# LED__V1_0.net
KiCad netlist of a schematic drawn in Altium Designer
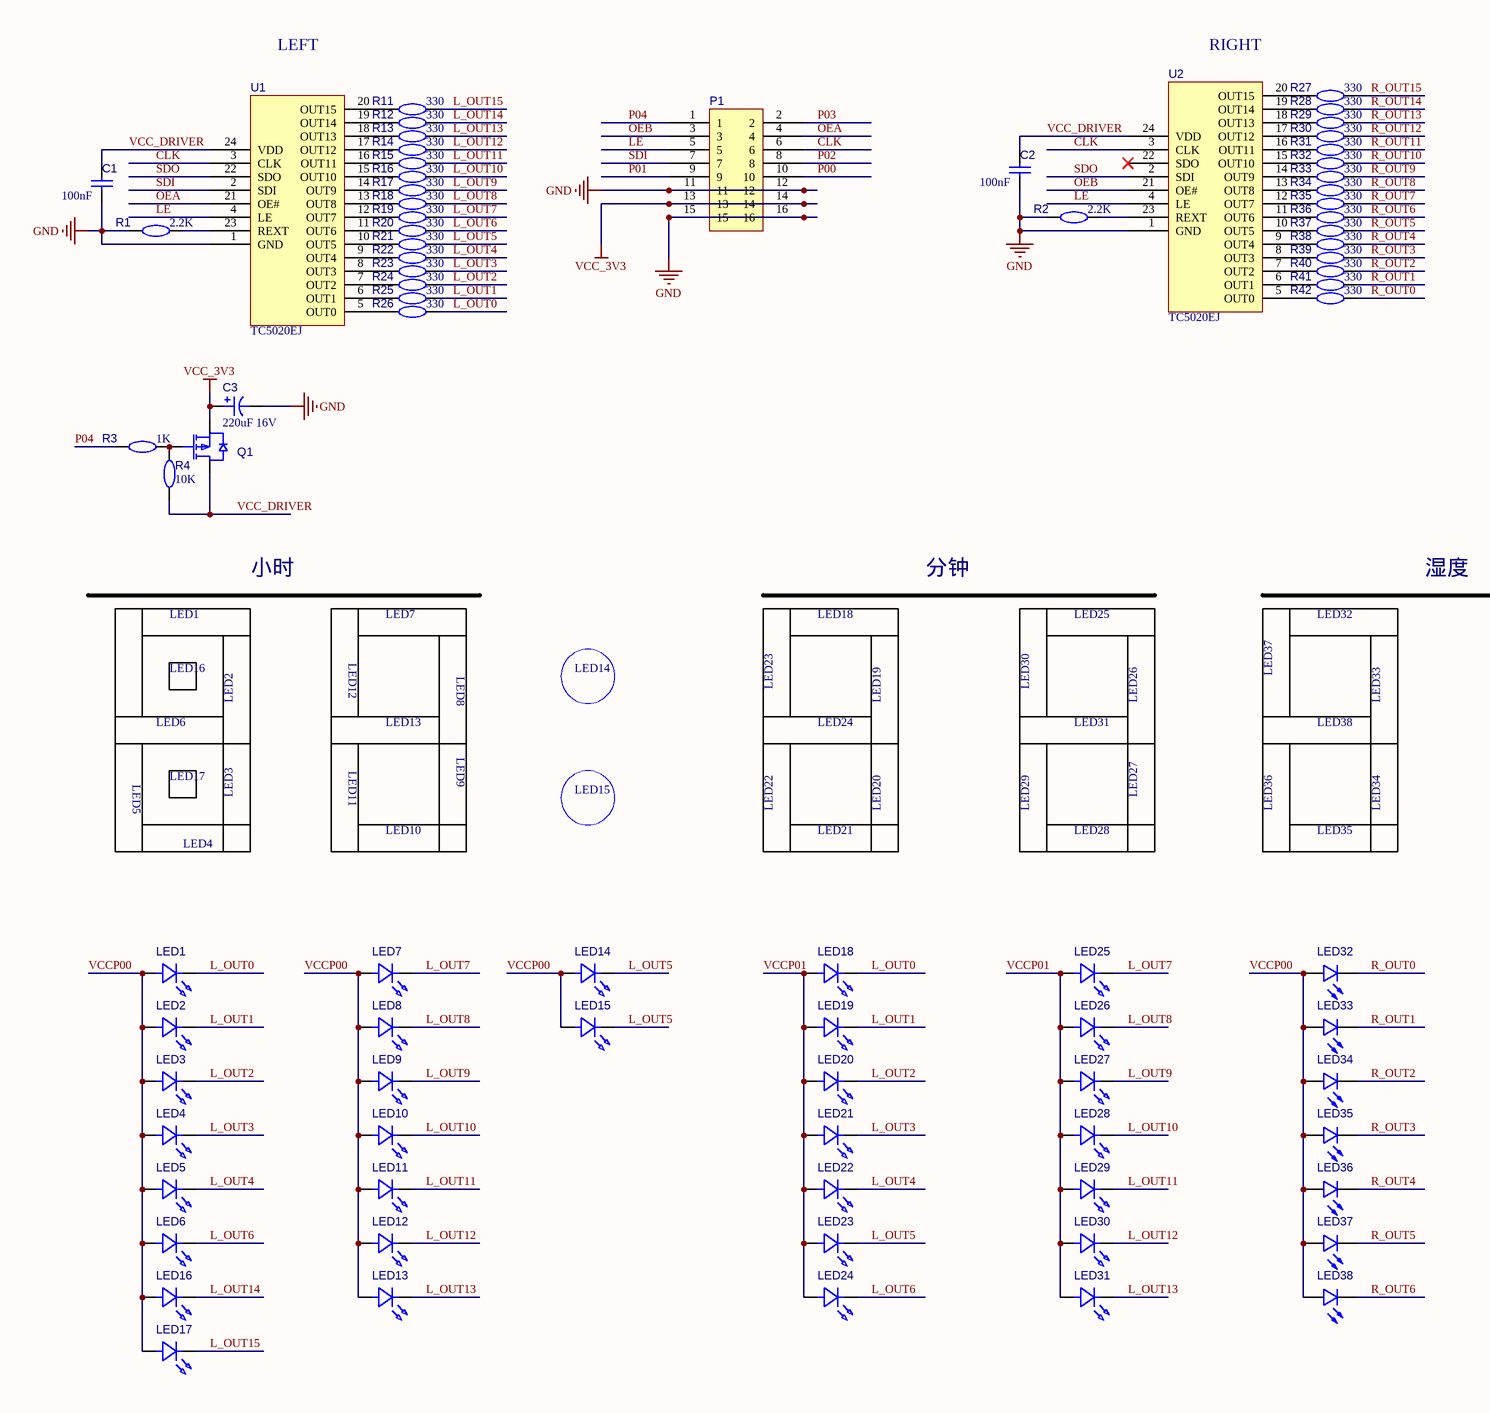
[diagram p0: LED显示灯板_V1.0.SchDoc, left]
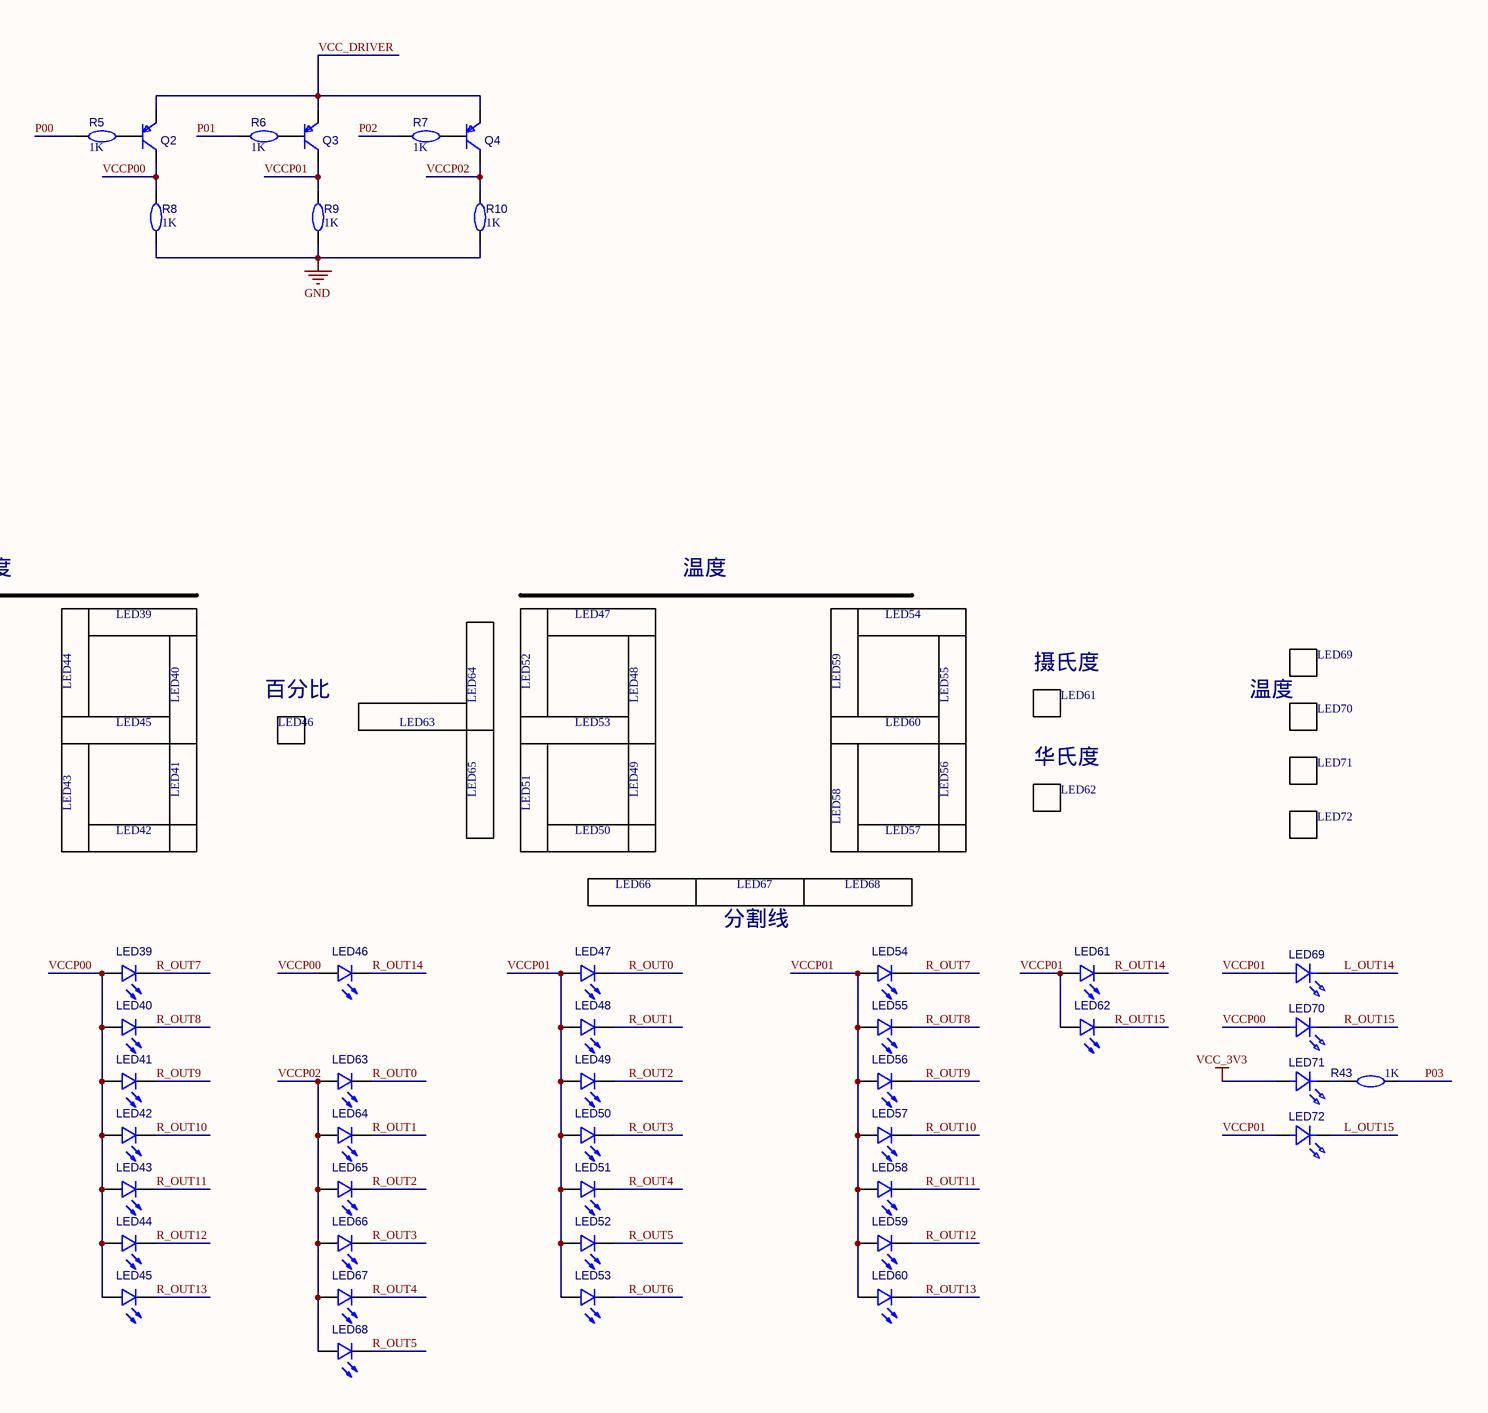
[diagram p1: LED显示灯板_V1.0.SchDoc, right]

(export (version "E")
  (design (tool "Eeschema 10.0.6"))
  (components
    (comp (ref "C1")
      (value "100nF")
      (footprint "C0603")
      (description "贴片电容")
      (libsource (lib "ADlib") (part "CAP_C0603_50V_10nF 50V"))
    )
    (comp (ref "C2")
      (value "100nF")
      (footprint "C0603")
      (description "贴片电容")
      (libsource (lib "ADlib") (part "CAP_C0603_50V_10nF 50V"))
    )
    (comp (ref "C3")
      (value "220uF 16V")
      (footprint "CAP-SMD_BD6.3-L6.6-W6.6-FD-1")
      (description "贴片型铝电解电容")
      (libsource (lib "ADlib") (part "CAP_ELEC_SMD_220U_16V"))
    )
    (comp (ref "LED1")
      (value "LED_WHITE_20MA_TBD")
      (footprint "LED0603")
      (description "发光二极管")
      (libsource (lib "ADlib") (part "LED_WHITE_20MA_TBD"))
    )
    (comp (ref "LED2")
      (value "LED_WHITE_20MA_TBD")
      (footprint "LED0603")
      (description "发光二极管")
      (libsource (lib "ADlib") (part "LED_WHITE_20MA_TBD"))
    )
    (comp (ref "LED3")
      (value "LED_WHITE_20MA_TBD")
      (footprint "LED0603")
      (description "发光二极管")
      (libsource (lib "ADlib") (part "LED_WHITE_20MA_TBD"))
    )
    (comp (ref "LED4")
      (value "LED_WHITE_20MA_TBD")
      (footprint "LED0603")
      (description "发光二极管")
      (libsource (lib "ADlib") (part "LED_WHITE_20MA_TBD"))
    )
    (comp (ref "LED5")
      (value "LED_WHITE_20MA_TBD")
      (footprint "LED0603")
      (description "发光二极管")
      (libsource (lib "ADlib") (part "LED_WHITE_20MA_TBD"))
    )
    (comp (ref "LED6")
      (value "LED_WHITE_20MA_TBD")
      (footprint "LED0603")
      (description "发光二极管")
      (libsource (lib "ADlib") (part "LED_WHITE_20MA_TBD"))
    )
    (comp (ref "LED7")
      (value "LED_WHITE_20MA_TBD")
      (footprint "LED0603")
      (description "发光二极管")
      (libsource (lib "ADlib") (part "LED_WHITE_20MA_TBD"))
    )
    (comp (ref "LED8")
      (value "LED_WHITE_20MA_TBD")
      (footprint "LED0603")
      (description "发光二极管")
      (libsource (lib "ADlib") (part "LED_WHITE_20MA_TBD"))
    )
    (comp (ref "LED9")
      (value "LED_WHITE_20MA_TBD")
      (footprint "LED0603")
      (description "发光二极管")
      (libsource (lib "ADlib") (part "LED_WHITE_20MA_TBD"))
    )
    (comp (ref "LED10")
      (value "LED_WHITE_20MA_TBD")
      (footprint "LED0603")
      (description "发光二极管")
      (libsource (lib "ADlib") (part "LED_WHITE_20MA_TBD"))
    )
    (comp (ref "LED11")
      (value "LED_WHITE_20MA_TBD")
      (footprint "LED0603")
      (description "发光二极管")
      (libsource (lib "ADlib") (part "LED_WHITE_20MA_TBD"))
    )
    (comp (ref "LED12")
      (value "LED_WHITE_20MA_TBD")
      (footprint "LED0603")
      (description "发光二极管")
      (libsource (lib "ADlib") (part "LED_WHITE_20MA_TBD"))
    )
    (comp (ref "LED13")
      (value "LED_WHITE_20MA_TBD")
      (footprint "LED0603")
      (description "发光二极管")
      (libsource (lib "ADlib") (part "LED_WHITE_20MA_TBD"))
    )
    (comp (ref "LED14")
      (value "LED_WHITE_20MA_TBD")
      (footprint "LED0603")
      (description "发光二极管")
      (libsource (lib "ADlib") (part "LED_WHITE_20MA_TBD"))
    )
    (comp (ref "LED15")
      (value "LED_WHITE_20MA_TBD")
      (footprint "LED0603")
      (description "发光二极管")
      (libsource (lib "ADlib") (part "LED_WHITE_20MA_TBD"))
    )
    (comp (ref "LED16")
      (value "LED_WHITE_20MA_TBD")
      (footprint "LED0603")
      (description "发光二极管")
      (libsource (lib "ADlib") (part "LED_WHITE_20MA_TBD"))
    )
    (comp (ref "LED17")
      (value "LED_WHITE_20MA_TBD")
      (footprint "LED0603")
      (description "发光二极管")
      (libsource (lib "ADlib") (part "LED_WHITE_20MA_TBD"))
    )
    (comp (ref "LED18")
      (value "LED_WHITE_20MA_TBD")
      (footprint "LED0603")
      (description "发光二极管")
      (libsource (lib "ADlib") (part "LED_WHITE_20MA_TBD"))
    )
    (comp (ref "LED19")
      (value "LED_WHITE_20MA_TBD")
      (footprint "LED0603")
      (description "发光二极管")
      (libsource (lib "ADlib") (part "LED_WHITE_20MA_TBD"))
    )
    (comp (ref "LED20")
      (value "LED_WHITE_20MA_TBD")
      (footprint "LED0603")
      (description "发光二极管")
      (libsource (lib "ADlib") (part "LED_WHITE_20MA_TBD"))
    )
    (comp (ref "LED21")
      (value "LED_WHITE_20MA_TBD")
      (footprint "LED0603")
      (description "发光二极管")
      (libsource (lib "ADlib") (part "LED_WHITE_20MA_TBD"))
    )
    (comp (ref "LED22")
      (value "LED_WHITE_20MA_TBD")
      (footprint "LED0603")
      (description "发光二极管")
      (libsource (lib "ADlib") (part "LED_WHITE_20MA_TBD"))
    )
    (comp (ref "LED23")
      (value "LED_WHITE_20MA_TBD")
      (footprint "LED0603")
      (description "发光二极管")
      (libsource (lib "ADlib") (part "LED_WHITE_20MA_TBD"))
    )
    (comp (ref "LED24")
      (value "LED_WHITE_20MA_TBD")
      (footprint "LED0603")
      (description "发光二极管")
      (libsource (lib "ADlib") (part "LED_WHITE_20MA_TBD"))
    )
    (comp (ref "LED25")
      (value "LED_WHITE_20MA_TBD")
      (footprint "LED0603")
      (description "发光二极管")
      (libsource (lib "ADlib") (part "LED_WHITE_20MA_TBD"))
    )
    (comp (ref "LED26")
      (value "LED_WHITE_20MA_TBD")
      (footprint "LED0603")
      (description "发光二极管")
      (libsource (lib "ADlib") (part "LED_WHITE_20MA_TBD"))
    )
    (comp (ref "LED27")
      (value "LED_WHITE_20MA_TBD")
      (footprint "LED0603")
      (description "发光二极管")
      (libsource (lib "ADlib") (part "LED_WHITE_20MA_TBD"))
    )
    (comp (ref "LED28")
      (value "LED_WHITE_20MA_TBD")
      (footprint "LED0603")
      (description "发光二极管")
      (libsource (lib "ADlib") (part "LED_WHITE_20MA_TBD"))
    )
    (comp (ref "LED29")
      (value "LED_WHITE_20MA_TBD")
      (footprint "LED0603")
      (description "发光二极管")
      (libsource (lib "ADlib") (part "LED_WHITE_20MA_TBD"))
    )
    (comp (ref "LED30")
      (value "LED_WHITE_20MA_TBD")
      (footprint "LED0603")
      (description "发光二极管")
      (libsource (lib "ADlib") (part "LED_WHITE_20MA_TBD"))
    )
    (comp (ref "LED31")
      (value "LED_WHITE_20MA_TBD")
      (footprint "LED0603")
      (description "发光二极管")
      (libsource (lib "ADlib") (part "LED_WHITE_20MA_TBD"))
    )
    (comp (ref "LED32")
      (value "LED BLUE")
      (footprint "LED0603")
      (description "发光二极管")
      (libsource (lib "ADlib") (part "LED_BLUE_10MA_TBD"))
    )
    (comp (ref "LED33")
      (value "LED BLUE")
      (footprint "LED0603")
      (description "发光二极管")
      (libsource (lib "ADlib") (part "LED_BLUE_10MA_TBD"))
    )
    (comp (ref "LED34")
      (value "LED BLUE")
      (footprint "LED0603")
      (description "发光二极管")
      (libsource (lib "ADlib") (part "LED_BLUE_10MA_TBD"))
    )
    (comp (ref "LED35")
      (value "LED BLUE")
      (footprint "LED0603")
      (description "发光二极管")
      (libsource (lib "ADlib") (part "LED_BLUE_10MA_TBD"))
    )
    (comp (ref "LED36")
      (value "LED BLUE")
      (footprint "LED0603")
      (description "发光二极管")
      (libsource (lib "ADlib") (part "LED_BLUE_10MA_TBD"))
    )
    (comp (ref "LED37")
      (value "LED BLUE")
      (footprint "LED0603")
      (description "发光二极管")
      (libsource (lib "ADlib") (part "LED_BLUE_10MA_TBD"))
    )
    (comp (ref "LED38")
      (value "LED BLUE")
      (footprint "LED0603")
      (description "发光二极管")
      (libsource (lib "ADlib") (part "LED_BLUE_10MA_TBD"))
    )
    (comp (ref "LED39")
      (value "LED BLUE")
      (footprint "LED0603")
      (description "发光二极管")
      (libsource (lib "ADlib") (part "LED_BLUE_10MA_TBD"))
    )
    (comp (ref "LED40")
      (value "LED BLUE")
      (footprint "LED0603")
      (description "发光二极管")
      (libsource (lib "ADlib") (part "LED_BLUE_10MA_TBD"))
    )
    (comp (ref "LED41")
      (value "LED BLUE")
      (footprint "LED0603")
      (description "发光二极管")
      (libsource (lib "ADlib") (part "LED_BLUE_10MA_TBD"))
    )
    (comp (ref "LED42")
      (value "LED BLUE")
      (footprint "LED0603")
      (description "发光二极管")
      (libsource (lib "ADlib") (part "LED_BLUE_10MA_TBD"))
    )
    (comp (ref "LED43")
      (value "LED BLUE")
      (footprint "LED0603")
      (description "发光二极管")
      (libsource (lib "ADlib") (part "LED_BLUE_10MA_TBD"))
    )
    (comp (ref "LED44")
      (value "LED BLUE")
      (footprint "LED0603")
      (description "发光二极管")
      (libsource (lib "ADlib") (part "LED_BLUE_10MA_TBD"))
    )
    (comp (ref "LED45")
      (value "LED BLUE")
      (footprint "LED0603")
      (description "发光二极管")
      (libsource (lib "ADlib") (part "LED_BLUE_10MA_TBD"))
    )
    (comp (ref "LED46")
      (value "LED BLUE")
      (footprint "LED0603")
      (description "发光二极管")
      (libsource (lib "ADlib") (part "LED_BLUE_10MA_TBD"))
    )
    (comp (ref "LED47")
      (value "LED BLUE")
      (footprint "LED0603")
      (description "发光二极管")
      (libsource (lib "ADlib") (part "LED_BLUE_10MA_TBD"))
    )
    (comp (ref "LED48")
      (value "LED BLUE")
      (footprint "LED0603")
      (description "发光二极管")
      (libsource (lib "ADlib") (part "LED_BLUE_10MA_TBD"))
    )
    (comp (ref "LED49")
      (value "LED BLUE")
      (footprint "LED0603")
      (description "发光二极管")
      (libsource (lib "ADlib") (part "LED_BLUE_10MA_TBD"))
    )
    (comp (ref "LED50")
      (value "LED BLUE")
      (footprint "LED0603")
      (description "发光二极管")
      (libsource (lib "ADlib") (part "LED_BLUE_10MA_TBD"))
    )
    (comp (ref "LED51")
      (value "LED BLUE")
      (footprint "LED0603")
      (description "发光二极管")
      (libsource (lib "ADlib") (part "LED_BLUE_10MA_TBD"))
    )
    (comp (ref "LED52")
      (value "LED BLUE")
      (footprint "LED0603")
      (description "发光二极管")
      (libsource (lib "ADlib") (part "LED_BLUE_10MA_TBD"))
    )
    (comp (ref "LED53")
      (value "LED BLUE")
      (footprint "LED0603")
      (description "发光二极管")
      (libsource (lib "ADlib") (part "LED_BLUE_10MA_TBD"))
    )
    (comp (ref "LED54")
      (value "LED BLUE")
      (footprint "LED0603")
      (description "发光二极管")
      (libsource (lib "ADlib") (part "LED_BLUE_10MA_TBD"))
    )
    (comp (ref "LED55")
      (value "LED BLUE")
      (footprint "LED0603")
      (description "发光二极管")
      (libsource (lib "ADlib") (part "LED_BLUE_10MA_TBD"))
    )
    (comp (ref "LED56")
      (value "LED BLUE")
      (footprint "LED0603")
      (description "发光二极管")
      (libsource (lib "ADlib") (part "LED_BLUE_10MA_TBD"))
    )
    (comp (ref "LED57")
      (value "LED BLUE")
      (footprint "LED0603")
      (description "发光二极管")
      (libsource (lib "ADlib") (part "LED_BLUE_10MA_TBD"))
    )
    (comp (ref "LED58")
      (value "LED BLUE")
      (footprint "LED0603")
      (description "发光二极管")
      (libsource (lib "ADlib") (part "LED_BLUE_10MA_TBD"))
    )
    (comp (ref "LED59")
      (value "LED BLUE")
      (footprint "LED0603")
      (description "发光二极管")
      (libsource (lib "ADlib") (part "LED_BLUE_10MA_TBD"))
    )
    (comp (ref "LED60")
      (value "LED BLUE")
      (footprint "LED0603")
      (description "发光二极管")
      (libsource (lib "ADlib") (part "LED_BLUE_10MA_TBD"))
    )
    (comp (ref "LED61")
      (value "LED BLUE")
      (footprint "LED0603")
      (description "发光二极管")
      (libsource (lib "ADlib") (part "LED_BLUE_10MA_TBD"))
    )
    (comp (ref "LED62")
      (value "LED BLUE")
      (footprint "LED0603")
      (description "发光二极管")
      (libsource (lib "ADlib") (part "LED_BLUE_10MA_TBD"))
    )
    (comp (ref "LED63")
      (value "LED BLUE")
      (footprint "LED0603")
      (description "发光二极管")
      (libsource (lib "ADlib") (part "LED_BLUE_10MA_TBD"))
    )
    (comp (ref "LED64")
      (value "LED BLUE")
      (footprint "LED0603")
      (description "发光二极管")
      (libsource (lib "ADlib") (part "LED_BLUE_10MA_TBD"))
    )
    (comp (ref "LED65")
      (value "LED BLUE")
      (footprint "LED0603")
      (description "发光二极管")
      (libsource (lib "ADlib") (part "LED_BLUE_10MA_TBD"))
    )
    (comp (ref "LED66")
      (value "LED BLUE")
      (footprint "LED0603")
      (description "发光二极管")
      (libsource (lib "ADlib") (part "LED_BLUE_10MA_TBD"))
    )
    (comp (ref "LED67")
      (value "LED BLUE")
      (footprint "LED0603")
      (description "发光二极管")
      (libsource (lib "ADlib") (part "LED_BLUE_10MA_TBD"))
    )
    (comp (ref "LED68")
      (value "LED BLUE")
      (footprint "LED0603")
      (description "发光二极管")
      (libsource (lib "ADlib") (part "LED_BLUE_10MA_TBD"))
    )
    (comp (ref "LED69")
      (value "LED_WHITE_20MA_TBD")
      (footprint "LED0603")
      (description "发光二极管")
      (libsource (lib "ADlib") (part "LED_WHITE_20MA_TBD"))
    )
    (comp (ref "LED70")
      (value "LED_WHITE_20MA_TBD")
      (footprint "LED0603")
      (description "发光二极管")
      (libsource (lib "ADlib") (part "LED_WHITE_20MA_TBD"))
    )
    (comp (ref "LED71")
      (value "LED_WHITE_20MA_TBD")
      (footprint "LED0603")
      (description "发光二极管")
      (libsource (lib "ADlib") (part "LED_WHITE_20MA_TBD"))
    )
    (comp (ref "LED72")
      (value "LED_WHITE_20MA_TBD")
      (footprint "LED0603")
      (description "发光二极管")
      (libsource (lib "ADlib") (part "LED_WHITE_20MA_TBD"))
    )
    (comp (ref "P1")
      (value "HEADER 2x8P 2.54mm")
      (footprint "IDC-TH_16P-P2.54-V-R2-C8-S2.54")
      (description "简牛座")
      (libsource (lib "ADlib") (part "HDR_2x08_2.54mm_IDC"))
    )
    (comp (ref "Q1")
      (value "P-MOSFET 30V 4A")
      (footprint "SOT-23_L2.9-W1.3-P1.90-LS2.4-BR")
      (description "P沟道场效应管")
      (libsource (lib "ADlib") (part "AO3401A"))
    )
    (comp (ref "Q2")
      (value "S8550")
      (footprint "SOT-23-3_L2.9-W1.3-P1.90-LS2.4-BR")
      (description "三极管PNP")
      (libsource (lib "ADlib") (part "S8550"))
    )
    (comp (ref "Q3")
      (value "S8550")
      (footprint "SOT-23-3_L2.9-W1.3-P1.90-LS2.4-BR")
      (description "三极管PNP")
      (libsource (lib "ADlib") (part "S8550"))
    )
    (comp (ref "Q4")
      (value "S8550")
      (footprint "SOT-23-3_L2.9-W1.3-P1.90-LS2.4-BR")
      (description "三极管PNP")
      (libsource (lib "ADlib") (part "S8550"))
    )
    (comp (ref "R1")
      (value "2.2K")
      (footprint "R0603")
      (description "贴片电阻")
      (libsource (lib "ADlib") (part "R_0603_100MW"))
    )
    (comp (ref "R2")
      (value "2.2K")
      (footprint "R0603")
      (description "贴片电阻")
      (libsource (lib "ADlib") (part "R_0603_100MW"))
    )
    (comp (ref "R3")
      (value "1K")
      (footprint "R0603")
      (description "贴片电阻")
      (libsource (lib "ADlib") (part "R_0603_100MW"))
    )
    (comp (ref "R4")
      (value "10K")
      (footprint "R0603")
      (description "贴片电阻")
      (libsource (lib "ADlib") (part "R_0603_100MW"))
    )
    (comp (ref "R5")
      (value "1K")
      (footprint "R0603")
      (description "贴片电阻")
      (libsource (lib "ADlib") (part "R_0603_100MW"))
    )
    (comp (ref "R6")
      (value "1K")
      (footprint "R0603")
      (description "贴片电阻")
      (libsource (lib "ADlib") (part "R_0603_100MW"))
    )
    (comp (ref "R7")
      (value "1K")
      (footprint "R0603")
      (description "贴片电阻")
      (libsource (lib "ADlib") (part "R_0603_100MW"))
    )
    (comp (ref "R8")
      (value "1K")
      (footprint "R0603")
      (description "贴片电阻")
      (libsource (lib "ADlib") (part "R_0603_100MW"))
    )
    (comp (ref "R9")
      (value "1K")
      (footprint "R0603")
      (description "贴片电阻")
      (libsource (lib "ADlib") (part "R_0603_100MW"))
    )
    (comp (ref "R10")
      (value "1K")
      (footprint "R0603")
      (description "贴片电阻")
      (libsource (lib "ADlib") (part "R_0603_100MW"))
    )
    (comp (ref "R11")
      (value "330")
      (footprint "R0603")
      (description "贴片电阻")
      (libsource (lib "ADlib") (part "R_0603_100MW"))
    )
    (comp (ref "R12")
      (value "330")
      (footprint "R0603")
      (description "贴片电阻")
      (libsource (lib "ADlib") (part "R_0603_100MW"))
    )
    (comp (ref "R13")
      (value "330")
      (footprint "R0603")
      (description "贴片电阻")
      (libsource (lib "ADlib") (part "R_0603_100MW"))
    )
    (comp (ref "R14")
      (value "330")
      (footprint "R0603")
      (description "贴片电阻")
      (libsource (lib "ADlib") (part "R_0603_100MW"))
    )
    (comp (ref "R15")
      (value "330")
      (footprint "R0603")
      (description "贴片电阻")
      (libsource (lib "ADlib") (part "R_0603_100MW"))
    )
    (comp (ref "R16")
      (value "330")
      (footprint "R0603")
      (description "贴片电阻")
      (libsource (lib "ADlib") (part "R_0603_100MW"))
    )
    (comp (ref "R17")
      (value "330")
      (footprint "R0603")
      (description "贴片电阻")
      (libsource (lib "ADlib") (part "R_0603_100MW"))
    )
    (comp (ref "R18")
      (value "330")
      (footprint "R0603")
      (description "贴片电阻")
      (libsource (lib "ADlib") (part "R_0603_100MW"))
    )
    (comp (ref "R19")
      (value "330")
      (footprint "R0603")
      (description "贴片电阻")
      (libsource (lib "ADlib") (part "R_0603_100MW"))
    )
    (comp (ref "R20")
      (value "330")
      (footprint "R0603")
      (description "贴片电阻")
      (libsource (lib "ADlib") (part "R_0603_100MW"))
    )
    (comp (ref "R21")
      (value "330")
      (footprint "R0603")
      (description "贴片电阻")
      (libsource (lib "ADlib") (part "R_0603_100MW"))
    )
    (comp (ref "R22")
      (value "330")
      (footprint "R0603")
      (description "贴片电阻")
      (libsource (lib "ADlib") (part "R_0603_100MW"))
    )
    (comp (ref "R23")
      (value "330")
      (footprint "R0603")
      (description "贴片电阻")
      (libsource (lib "ADlib") (part "R_0603_100MW"))
    )
    (comp (ref "R24")
      (value "330")
      (footprint "R0603")
      (description "贴片电阻")
      (libsource (lib "ADlib") (part "R_0603_100MW"))
    )
    (comp (ref "R25")
      (value "330")
      (footprint "R0603")
      (description "贴片电阻")
      (libsource (lib "ADlib") (part "R_0603_100MW"))
    )
    (comp (ref "R26")
      (value "330")
      (footprint "R0603")
      (description "贴片电阻")
      (libsource (lib "ADlib") (part "R_0603_100MW"))
    )
    (comp (ref "R27")
      (value "330")
      (footprint "R0603")
      (description "贴片电阻")
      (libsource (lib "ADlib") (part "R_0603_100MW"))
    )
    (comp (ref "R28")
      (value "330")
      (footprint "R0603")
      (description "贴片电阻")
      (libsource (lib "ADlib") (part "R_0603_100MW"))
    )
    (comp (ref "R29")
      (value "330")
      (footprint "R0603")
      (description "贴片电阻")
      (libsource (lib "ADlib") (part "R_0603_100MW"))
    )
    (comp (ref "R30")
      (value "330")
      (footprint "R0603")
      (description "贴片电阻")
      (libsource (lib "ADlib") (part "R_0603_100MW"))
    )
    (comp (ref "R31")
      (value "330")
      (footprint "R0603")
      (description "贴片电阻")
      (libsource (lib "ADlib") (part "R_0603_100MW"))
    )
    (comp (ref "R32")
      (value "330")
      (footprint "R0603")
      (description "贴片电阻")
      (libsource (lib "ADlib") (part "R_0603_100MW"))
    )
    (comp (ref "R33")
      (value "330")
      (footprint "R0603")
      (description "贴片电阻")
      (libsource (lib "ADlib") (part "R_0603_100MW"))
    )
    (comp (ref "R34")
      (value "330")
      (footprint "R0603")
      (description "贴片电阻")
      (libsource (lib "ADlib") (part "R_0603_100MW"))
    )
    (comp (ref "R35")
      (value "330")
      (footprint "R0603")
      (description "贴片电阻")
      (libsource (lib "ADlib") (part "R_0603_100MW"))
    )
    (comp (ref "R36")
      (value "330")
      (footprint "R0603")
      (description "贴片电阻")
      (libsource (lib "ADlib") (part "R_0603_100MW"))
    )
    (comp (ref "R37")
      (value "330")
      (footprint "R0603")
      (description "贴片电阻")
      (libsource (lib "ADlib") (part "R_0603_100MW"))
    )
    (comp (ref "R38")
      (value "330")
      (footprint "R0603")
      (description "贴片电阻")
      (libsource (lib "ADlib") (part "R_0603_100MW"))
    )
    (comp (ref "R39")
      (value "330")
      (footprint "R0603")
      (description "贴片电阻")
      (libsource (lib "ADlib") (part "R_0603_100MW"))
    )
    (comp (ref "R40")
      (value "330")
      (footprint "R0603")
      (description "贴片电阻")
      (libsource (lib "ADlib") (part "R_0603_100MW"))
    )
    (comp (ref "R41")
      (value "330")
      (footprint "R0603")
      (description "贴片电阻")
      (libsource (lib "ADlib") (part "R_0603_100MW"))
    )
    (comp (ref "R42")
      (value "330")
      (footprint "R0603")
      (description "贴片电阻")
      (libsource (lib "ADlib") (part "R_0603_100MW"))
    )
    (comp (ref "R43")
      (value "1K")
      (footprint "R0603")
      (description "贴片电阻")
      (libsource (lib "ADlib") (part "R_0603_100MW"))
    )
    (comp (ref "U1")
      (value "TC5020EJ")
      (footprint "SSOP-24_L8.7-W3.9-P0.64-LS6.0-BL")
      (description "LED 驱动芯片")
      (libsource (lib "ADlib") (part "TC5020EJ"))
    )
    (comp (ref "U2")
      (value "TC5020EJ")
      (footprint "SSOP-24_L8.7-W3.9-P0.64-LS6.0-BL")
      (description "LED 驱动芯片")
      (libsource (lib "ADlib") (part "TC5020EJ"))
    )
  )
  (nets
    (net (code "1") (name "/CLK") (class "Default")
      (node (ref "P1") (pin "6") (pinfunction "6_6") (pintype "passive"))
      (node (ref "U1") (pin "3") (pinfunction "CLK_3") (pintype "passive"))
      (node (ref "U2") (pin "3") (pinfunction "CLK_3") (pintype "passive"))
    )
    (net (code "2") (name "/LE") (class "Default")
      (node (ref "P1") (pin "5") (pinfunction "5_5") (pintype "passive"))
      (node (ref "U1") (pin "4") (pinfunction "LE_4") (pintype "passive"))
      (node (ref "U2") (pin "4") (pinfunction "LE_4") (pintype "passive"))
    )
    (net (code "3") (name "/L_OUT0") (class "Default")
      (node (ref "LED1") (pin "1") (pinfunction "K_1") (pintype "passive"))
      (node (ref "LED18") (pin "1") (pinfunction "K_1") (pintype "passive"))
      (node (ref "R26") (pin "2") (pinfunction "2_2") (pintype "passive"))
    )
    (net (code "4") (name "/L_OUT1") (class "Default")
      (node (ref "LED19") (pin "1") (pinfunction "K_1") (pintype "passive"))
      (node (ref "LED2") (pin "1") (pinfunction "K_1") (pintype "passive"))
      (node (ref "R25") (pin "2") (pinfunction "2_2") (pintype "passive"))
    )
    (net (code "5") (name "/L_OUT2") (class "Default")
      (node (ref "LED20") (pin "1") (pinfunction "K_1") (pintype "passive"))
      (node (ref "LED3") (pin "1") (pinfunction "K_1") (pintype "passive"))
      (node (ref "R24") (pin "2") (pinfunction "2_2") (pintype "passive"))
    )
    (net (code "6") (name "/L_OUT3") (class "Default")
      (node (ref "LED21") (pin "1") (pinfunction "K_1") (pintype "passive"))
      (node (ref "LED4") (pin "1") (pinfunction "K_1") (pintype "passive"))
      (node (ref "R23") (pin "2") (pinfunction "2_2") (pintype "passive"))
    )
    (net (code "7") (name "/L_OUT4") (class "Default")
      (node (ref "LED22") (pin "1") (pinfunction "K_1") (pintype "passive"))
      (node (ref "LED5") (pin "1") (pinfunction "K_1") (pintype "passive"))
      (node (ref "R22") (pin "2") (pinfunction "2_2") (pintype "passive"))
    )
    (net (code "8") (name "/L_OUT5") (class "Default")
      (node (ref "LED14") (pin "1") (pinfunction "K_1") (pintype "passive"))
      (node (ref "LED15") (pin "1") (pinfunction "K_1") (pintype "passive"))
      (node (ref "LED23") (pin "1") (pinfunction "K_1") (pintype "passive"))
      (node (ref "R21") (pin "2") (pinfunction "2_2") (pintype "passive"))
    )
    (net (code "9") (name "/L_OUT6") (class "Default")
      (node (ref "LED24") (pin "1") (pinfunction "K_1") (pintype "passive"))
      (node (ref "LED6") (pin "1") (pinfunction "K_1") (pintype "passive"))
      (node (ref "R20") (pin "2") (pinfunction "2_2") (pintype "passive"))
    )
    (net (code "10") (name "/L_OUT7") (class "Default")
      (node (ref "LED25") (pin "1") (pinfunction "K_1") (pintype "passive"))
      (node (ref "LED7") (pin "1") (pinfunction "K_1") (pintype "passive"))
      (node (ref "R19") (pin "2") (pinfunction "2_2") (pintype "passive"))
    )
    (net (code "11") (name "/L_OUT8") (class "Default")
      (node (ref "LED26") (pin "1") (pinfunction "K_1") (pintype "passive"))
      (node (ref "LED8") (pin "1") (pinfunction "K_1") (pintype "passive"))
      (node (ref "R18") (pin "2") (pinfunction "2_2") (pintype "passive"))
    )
    (net (code "12") (name "/L_OUT9") (class "Default")
      (node (ref "LED27") (pin "1") (pinfunction "K_1") (pintype "passive"))
      (node (ref "LED9") (pin "1") (pinfunction "K_1") (pintype "passive"))
      (node (ref "R17") (pin "2") (pinfunction "2_2") (pintype "passive"))
    )
    (net (code "13") (name "/L_OUT10") (class "Default")
      (node (ref "LED10") (pin "1") (pinfunction "K_1") (pintype "passive"))
      (node (ref "LED28") (pin "1") (pinfunction "K_1") (pintype "passive"))
      (node (ref "R16") (pin "2") (pinfunction "2_2") (pintype "passive"))
    )
    (net (code "14") (name "/L_OUT11") (class "Default")
      (node (ref "LED11") (pin "1") (pinfunction "K_1") (pintype "passive"))
      (node (ref "LED29") (pin "1") (pinfunction "K_1") (pintype "passive"))
      (node (ref "R15") (pin "2") (pinfunction "2_2") (pintype "passive"))
    )
    (net (code "15") (name "/L_OUT12") (class "Default")
      (node (ref "LED12") (pin "1") (pinfunction "K_1") (pintype "passive"))
      (node (ref "LED30") (pin "1") (pinfunction "K_1") (pintype "passive"))
      (node (ref "R14") (pin "2") (pinfunction "2_2") (pintype "passive"))
    )
    (net (code "16") (name "/L_OUT13") (class "Default")
      (node (ref "LED13") (pin "1") (pinfunction "K_1") (pintype "passive"))
      (node (ref "LED31") (pin "1") (pinfunction "K_1") (pintype "passive"))
      (node (ref "R13") (pin "2") (pinfunction "2_2") (pintype "passive"))
    )
    (net (code "17") (name "/L_OUT14") (class "Default")
      (node (ref "LED16") (pin "1") (pinfunction "K_1") (pintype "passive"))
      (node (ref "LED69") (pin "1") (pinfunction "K_1") (pintype "passive"))
      (node (ref "R12") (pin "2") (pinfunction "2_2") (pintype "passive"))
    )
    (net (code "18") (name "/L_OUT15") (class "Default")
      (node (ref "LED17") (pin "1") (pinfunction "K_1") (pintype "passive"))
      (node (ref "LED72") (pin "1") (pinfunction "K_1") (pintype "passive"))
      (node (ref "R11") (pin "2") (pinfunction "2_2") (pintype "passive"))
    )
    (net (code "19") (name "/OEA") (class "Default")
      (node (ref "P1") (pin "4") (pinfunction "4_4") (pintype "passive"))
      (node (ref "U1") (pin "21") (pinfunction "OE#_21") (pintype "passive"))
    )
    (net (code "20") (name "/OEB") (class "Default")
      (node (ref "P1") (pin "3") (pinfunction "3_3") (pintype "passive"))
      (node (ref "U2") (pin "21") (pinfunction "OE#_21") (pintype "passive"))
    )
    (net (code "21") (name "/P00") (class "Default")
      (node (ref "P1") (pin "10") (pinfunction "10_10") (pintype "passive"))
      (node (ref "R5") (pin "2") (pinfunction "2_2") (pintype "passive"))
    )
    (net (code "22") (name "/P01") (class "Default")
      (node (ref "P1") (pin "9") (pinfunction "9_9") (pintype "passive"))
      (node (ref "R6") (pin "2") (pinfunction "2_2") (pintype "passive"))
    )
    (net (code "23") (name "/P02") (class "Default")
      (node (ref "P1") (pin "8") (pinfunction "8_8") (pintype "passive"))
      (node (ref "R7") (pin "2") (pinfunction "2_2") (pintype "passive"))
    )
    (net (code "24") (name "/P03") (class "Default")
      (node (ref "P1") (pin "2") (pinfunction "2_2") (pintype "passive"))
      (node (ref "R43") (pin "2") (pinfunction "2_2") (pintype "passive"))
    )
    (net (code "25") (name "/P04") (class "Default")
      (node (ref "P1") (pin "1") (pinfunction "1_1") (pintype "passive"))
      (node (ref "R3") (pin "1") (pinfunction "1_1") (pintype "passive"))
    )
    (net (code "26") (name "/R_OUT0") (class "Default")
      (node (ref "LED32") (pin "1") (pinfunction "-_1") (pintype "passive"))
      (node (ref "LED47") (pin "1") (pinfunction "-_1") (pintype "passive"))
      (node (ref "LED63") (pin "1") (pinfunction "-_1") (pintype "passive"))
      (node (ref "R42") (pin "2") (pinfunction "2_2") (pintype "passive"))
    )
    (net (code "27") (name "/R_OUT1") (class "Default")
      (node (ref "LED33") (pin "1") (pinfunction "-_1") (pintype "passive"))
      (node (ref "LED48") (pin "1") (pinfunction "-_1") (pintype "passive"))
      (node (ref "LED64") (pin "1") (pinfunction "-_1") (pintype "passive"))
      (node (ref "R41") (pin "2") (pinfunction "2_2") (pintype "passive"))
    )
    (net (code "28") (name "/R_OUT2") (class "Default")
      (node (ref "LED34") (pin "1") (pinfunction "-_1") (pintype "passive"))
      (node (ref "LED49") (pin "1") (pinfunction "-_1") (pintype "passive"))
      (node (ref "LED65") (pin "1") (pinfunction "-_1") (pintype "passive"))
      (node (ref "R40") (pin "2") (pinfunction "2_2") (pintype "passive"))
    )
    (net (code "29") (name "/R_OUT3") (class "Default")
      (node (ref "LED35") (pin "1") (pinfunction "-_1") (pintype "passive"))
      (node (ref "LED50") (pin "1") (pinfunction "-_1") (pintype "passive"))
      (node (ref "LED66") (pin "1") (pinfunction "-_1") (pintype "passive"))
      (node (ref "R39") (pin "2") (pinfunction "2_2") (pintype "passive"))
    )
    (net (code "30") (name "/R_OUT4") (class "Default")
      (node (ref "LED36") (pin "1") (pinfunction "-_1") (pintype "passive"))
      (node (ref "LED51") (pin "1") (pinfunction "-_1") (pintype "passive"))
      (node (ref "LED67") (pin "1") (pinfunction "-_1") (pintype "passive"))
      (node (ref "R38") (pin "2") (pinfunction "2_2") (pintype "passive"))
    )
    (net (code "31") (name "/R_OUT5") (class "Default")
      (node (ref "LED37") (pin "1") (pinfunction "-_1") (pintype "passive"))
      (node (ref "LED52") (pin "1") (pinfunction "-_1") (pintype "passive"))
      (node (ref "LED68") (pin "1") (pinfunction "-_1") (pintype "passive"))
      (node (ref "R37") (pin "2") (pinfunction "2_2") (pintype "passive"))
    )
    (net (code "32") (name "/R_OUT6") (class "Default")
      (node (ref "LED38") (pin "1") (pinfunction "-_1") (pintype "passive"))
      (node (ref "LED53") (pin "1") (pinfunction "-_1") (pintype "passive"))
      (node (ref "R36") (pin "2") (pinfunction "2_2") (pintype "passive"))
    )
    (net (code "33") (name "/R_OUT7") (class "Default")
      (node (ref "LED39") (pin "1") (pinfunction "-_1") (pintype "passive"))
      (node (ref "LED54") (pin "1") (pinfunction "-_1") (pintype "passive"))
      (node (ref "R35") (pin "2") (pinfunction "2_2") (pintype "passive"))
    )
    (net (code "34") (name "/R_OUT8") (class "Default")
      (node (ref "LED40") (pin "1") (pinfunction "-_1") (pintype "passive"))
      (node (ref "LED55") (pin "1") (pinfunction "-_1") (pintype "passive"))
      (node (ref "R34") (pin "2") (pinfunction "2_2") (pintype "passive"))
    )
    (net (code "35") (name "/R_OUT9") (class "Default")
      (node (ref "LED41") (pin "1") (pinfunction "-_1") (pintype "passive"))
      (node (ref "LED56") (pin "1") (pinfunction "-_1") (pintype "passive"))
      (node (ref "R33") (pin "2") (pinfunction "2_2") (pintype "passive"))
    )
    (net (code "36") (name "/R_OUT10") (class "Default")
      (node (ref "LED42") (pin "1") (pinfunction "-_1") (pintype "passive"))
      (node (ref "LED57") (pin "1") (pinfunction "-_1") (pintype "passive"))
      (node (ref "R32") (pin "2") (pinfunction "2_2") (pintype "passive"))
    )
    (net (code "37") (name "/R_OUT11") (class "Default")
      (node (ref "LED43") (pin "1") (pinfunction "-_1") (pintype "passive"))
      (node (ref "LED58") (pin "1") (pinfunction "-_1") (pintype "passive"))
      (node (ref "R31") (pin "2") (pinfunction "2_2") (pintype "passive"))
    )
    (net (code "38") (name "/R_OUT12") (class "Default")
      (node (ref "LED44") (pin "1") (pinfunction "-_1") (pintype "passive"))
      (node (ref "LED59") (pin "1") (pinfunction "-_1") (pintype "passive"))
      (node (ref "R30") (pin "2") (pinfunction "2_2") (pintype "passive"))
    )
    (net (code "39") (name "/R_OUT13") (class "Default")
      (node (ref "LED45") (pin "1") (pinfunction "-_1") (pintype "passive"))
      (node (ref "LED60") (pin "1") (pinfunction "-_1") (pintype "passive"))
      (node (ref "R29") (pin "2") (pinfunction "2_2") (pintype "passive"))
    )
    (net (code "40") (name "/R_OUT14") (class "Default")
      (node (ref "LED46") (pin "1") (pinfunction "-_1") (pintype "passive"))
      (node (ref "LED61") (pin "1") (pinfunction "-_1") (pintype "passive"))
      (node (ref "R28") (pin "2") (pinfunction "2_2") (pintype "passive"))
    )
    (net (code "41") (name "/R_OUT15") (class "Default")
      (node (ref "LED62") (pin "1") (pinfunction "-_1") (pintype "passive"))
      (node (ref "LED70") (pin "1") (pinfunction "K_1") (pintype "passive"))
      (node (ref "R27") (pin "2") (pinfunction "2_2") (pintype "passive"))
    )
    (net (code "42") (name "/SDI") (class "Default")
      (node (ref "P1") (pin "7") (pinfunction "7_7") (pintype "passive"))
      (node (ref "U1") (pin "2") (pinfunction "SDI_2") (pintype "passive"))
    )
    (net (code "43") (name "/SDO") (class "Default")
      (node (ref "U1") (pin "22") (pinfunction "SDO_22") (pintype "passive"))
      (node (ref "U2") (pin "2") (pinfunction "SDI_2") (pintype "passive"))
    )
    (net (code "44") (name "/VCCP00") (class "Default")
      (node (ref "LED1") (pin "2") (pinfunction "A_2") (pintype "passive"))
      (node (ref "LED10") (pin "2") (pinfunction "A_2") (pintype "passive"))
      (node (ref "LED11") (pin "2") (pinfunction "A_2") (pintype "passive"))
      (node (ref "LED12") (pin "2") (pinfunction "A_2") (pintype "passive"))
      (node (ref "LED13") (pin "2") (pinfunction "A_2") (pintype "passive"))
      (node (ref "LED14") (pin "2") (pinfunction "A_2") (pintype "passive"))
      (node (ref "LED15") (pin "2") (pinfunction "A_2") (pintype "passive"))
      (node (ref "LED16") (pin "2") (pinfunction "A_2") (pintype "passive"))
      (node (ref "LED17") (pin "2") (pinfunction "A_2") (pintype "passive"))
      (node (ref "LED2") (pin "2") (pinfunction "A_2") (pintype "passive"))
      (node (ref "LED3") (pin "2") (pinfunction "A_2") (pintype "passive"))
      (node (ref "LED32") (pin "2") (pinfunction "+_2") (pintype "passive"))
      (node (ref "LED33") (pin "2") (pinfunction "+_2") (pintype "passive"))
      (node (ref "LED34") (pin "2") (pinfunction "+_2") (pintype "passive"))
      (node (ref "LED35") (pin "2") (pinfunction "+_2") (pintype "passive"))
      (node (ref "LED36") (pin "2") (pinfunction "+_2") (pintype "passive"))
      (node (ref "LED37") (pin "2") (pinfunction "+_2") (pintype "passive"))
      (node (ref "LED38") (pin "2") (pinfunction "+_2") (pintype "passive"))
      (node (ref "LED39") (pin "2") (pinfunction "+_2") (pintype "passive"))
      (node (ref "LED4") (pin "2") (pinfunction "A_2") (pintype "passive"))
      (node (ref "LED40") (pin "2") (pinfunction "+_2") (pintype "passive"))
      (node (ref "LED41") (pin "2") (pinfunction "+_2") (pintype "passive"))
      (node (ref "LED42") (pin "2") (pinfunction "+_2") (pintype "passive"))
      (node (ref "LED43") (pin "2") (pinfunction "+_2") (pintype "passive"))
      (node (ref "LED44") (pin "2") (pinfunction "+_2") (pintype "passive"))
      (node (ref "LED45") (pin "2") (pinfunction "+_2") (pintype "passive"))
      (node (ref "LED46") (pin "2") (pinfunction "+_2") (pintype "passive"))
      (node (ref "LED5") (pin "2") (pinfunction "A_2") (pintype "passive"))
      (node (ref "LED6") (pin "2") (pinfunction "A_2") (pintype "passive"))
      (node (ref "LED7") (pin "2") (pinfunction "A_2") (pintype "passive"))
      (node (ref "LED70") (pin "2") (pinfunction "A_2") (pintype "passive"))
      (node (ref "LED8") (pin "2") (pinfunction "A_2") (pintype "passive"))
      (node (ref "LED9") (pin "2") (pinfunction "A_2") (pintype "passive"))
      (node (ref "Q2") (pin "3") (pinfunction "C_3") (pintype "passive"))
      (node (ref "R8") (pin "1") (pinfunction "1_1") (pintype "passive"))
    )
    (net (code "45") (name "/VCCP01") (class "Default")
      (node (ref "LED18") (pin "2") (pinfunction "A_2") (pintype "passive"))
      (node (ref "LED19") (pin "2") (pinfunction "A_2") (pintype "passive"))
      (node (ref "LED20") (pin "2") (pinfunction "A_2") (pintype "passive"))
      (node (ref "LED21") (pin "2") (pinfunction "A_2") (pintype "passive"))
      (node (ref "LED22") (pin "2") (pinfunction "A_2") (pintype "passive"))
      (node (ref "LED23") (pin "2") (pinfunction "A_2") (pintype "passive"))
      (node (ref "LED24") (pin "2") (pinfunction "A_2") (pintype "passive"))
      (node (ref "LED25") (pin "2") (pinfunction "A_2") (pintype "passive"))
      (node (ref "LED26") (pin "2") (pinfunction "A_2") (pintype "passive"))
      (node (ref "LED27") (pin "2") (pinfunction "A_2") (pintype "passive"))
      (node (ref "LED28") (pin "2") (pinfunction "A_2") (pintype "passive"))
      (node (ref "LED29") (pin "2") (pinfunction "A_2") (pintype "passive"))
      (node (ref "LED30") (pin "2") (pinfunction "A_2") (pintype "passive"))
      (node (ref "LED31") (pin "2") (pinfunction "A_2") (pintype "passive"))
      (node (ref "LED47") (pin "2") (pinfunction "+_2") (pintype "passive"))
      (node (ref "LED48") (pin "2") (pinfunction "+_2") (pintype "passive"))
      (node (ref "LED49") (pin "2") (pinfunction "+_2") (pintype "passive"))
      (node (ref "LED50") (pin "2") (pinfunction "+_2") (pintype "passive"))
      (node (ref "LED51") (pin "2") (pinfunction "+_2") (pintype "passive"))
      (node (ref "LED52") (pin "2") (pinfunction "+_2") (pintype "passive"))
      (node (ref "LED53") (pin "2") (pinfunction "+_2") (pintype "passive"))
      (node (ref "LED54") (pin "2") (pinfunction "+_2") (pintype "passive"))
      (node (ref "LED55") (pin "2") (pinfunction "+_2") (pintype "passive"))
      (node (ref "LED56") (pin "2") (pinfunction "+_2") (pintype "passive"))
      (node (ref "LED57") (pin "2") (pinfunction "+_2") (pintype "passive"))
      (node (ref "LED58") (pin "2") (pinfunction "+_2") (pintype "passive"))
      (node (ref "LED59") (pin "2") (pinfunction "+_2") (pintype "passive"))
      (node (ref "LED60") (pin "2") (pinfunction "+_2") (pintype "passive"))
      (node (ref "LED61") (pin "2") (pinfunction "+_2") (pintype "passive"))
      (node (ref "LED62") (pin "2") (pinfunction "+_2") (pintype "passive"))
      (node (ref "LED69") (pin "2") (pinfunction "A_2") (pintype "passive"))
      (node (ref "LED72") (pin "2") (pinfunction "A_2") (pintype "passive"))
      (node (ref "Q3") (pin "3") (pinfunction "C_3") (pintype "passive"))
      (node (ref "R9") (pin "1") (pinfunction "1_1") (pintype "passive"))
    )
    (net (code "46") (name "/VCCP02") (class "Default")
      (node (ref "LED63") (pin "2") (pinfunction "+_2") (pintype "passive"))
      (node (ref "LED64") (pin "2") (pinfunction "+_2") (pintype "passive"))
      (node (ref "LED65") (pin "2") (pinfunction "+_2") (pintype "passive"))
      (node (ref "LED66") (pin "2") (pinfunction "+_2") (pintype "passive"))
      (node (ref "LED67") (pin "2") (pinfunction "+_2") (pintype "passive"))
      (node (ref "LED68") (pin "2") (pinfunction "+_2") (pintype "passive"))
      (node (ref "Q4") (pin "3") (pinfunction "C_3") (pintype "passive"))
      (node (ref "R10") (pin "1") (pinfunction "1_1") (pintype "passive"))
    )
    (net (code "47") (name "/VCC_DRIVER") (class "Default")
      (node (ref "C1") (pin "2") (pinfunction "2_2") (pintype "passive"))
      (node (ref "C2") (pin "2") (pinfunction "2_2") (pintype "passive"))
      (node (ref "Q1") (pin "3") (pinfunction "D_3") (pintype "passive"))
      (node (ref "Q2") (pin "2") (pinfunction "E_2") (pintype "passive"))
      (node (ref "Q3") (pin "2") (pinfunction "E_2") (pintype "passive"))
      (node (ref "Q4") (pin "2") (pinfunction "E_2") (pintype "passive"))
      (node (ref "R4") (pin "1") (pinfunction "1_1") (pintype "passive"))
      (node (ref "U1") (pin "24") (pinfunction "VDD_24") (pintype "passive"))
      (node (ref "U2") (pin "24") (pinfunction "VDD_24") (pintype "passive"))
    )
    (net (code "48") (name "GND") (class "Default")
      (node (ref "C1") (pin "1") (pinfunction "1_1") (pintype "passive"))
      (node (ref "C2") (pin "1") (pinfunction "1_1") (pintype "passive"))
      (node (ref "C3") (pin "2") (pinfunction "2_2") (pintype "passive"))
      (node (ref "P1") (pin "11") (pinfunction "11_11") (pintype "passive"))
      (node (ref "P1") (pin "12") (pinfunction "12_12") (pintype "passive"))
      (node (ref "P1") (pin "15") (pinfunction "15_15") (pintype "passive"))
      (node (ref "P1") (pin "16") (pinfunction "16_16") (pintype "passive"))
      (node (ref "R1") (pin "1") (pinfunction "1_1") (pintype "passive"))
      (node (ref "R10") (pin "2") (pinfunction "2_2") (pintype "passive"))
      (node (ref "R2") (pin "1") (pinfunction "1_1") (pintype "passive"))
      (node (ref "R8") (pin "2") (pinfunction "2_2") (pintype "passive"))
      (node (ref "R9") (pin "2") (pinfunction "2_2") (pintype "passive"))
      (node (ref "U1") (pin "1") (pinfunction "GND_1") (pintype "passive"))
      (node (ref "U2") (pin "1") (pinfunction "GND_1") (pintype "passive"))
    )
    (net (code "49") (name "Net-(LED71-K)") (class "Default")
      (node (ref "LED71") (pin "1") (pinfunction "K_1") (pintype "passive"))
      (node (ref "R43") (pin "1") (pinfunction "1_1") (pintype "passive"))
    )
    (net (code "50") (name "Net-(Q1-G)") (class "Default")
      (node (ref "Q1") (pin "1") (pinfunction "G_1") (pintype "passive"))
      (node (ref "R3") (pin "2") (pinfunction "2_2") (pintype "passive"))
      (node (ref "R4") (pin "2") (pinfunction "2_2") (pintype "passive"))
    )
    (net (code "51") (name "Net-(Q2-B)") (class "Default")
      (node (ref "Q2") (pin "1") (pinfunction "B_1") (pintype "passive"))
      (node (ref "R5") (pin "1") (pinfunction "1_1") (pintype "passive"))
    )
    (net (code "52") (name "Net-(Q3-B)") (class "Default")
      (node (ref "Q3") (pin "1") (pinfunction "B_1") (pintype "passive"))
      (node (ref "R6") (pin "1") (pinfunction "1_1") (pintype "passive"))
    )
    (net (code "53") (name "Net-(Q4-B)") (class "Default")
      (node (ref "Q4") (pin "1") (pinfunction "B_1") (pintype "passive"))
      (node (ref "R7") (pin "1") (pinfunction "1_1") (pintype "passive"))
    )
    (net (code "54") (name "Net-(U1-OUT0)") (class "Default")
      (node (ref "R26") (pin "1") (pinfunction "1_1") (pintype "passive"))
      (node (ref "U1") (pin "5") (pinfunction "OUT0_5") (pintype "passive"))
    )
    (net (code "55") (name "Net-(U1-OUT1)") (class "Default")
      (node (ref "R25") (pin "1") (pinfunction "1_1") (pintype "passive"))
      (node (ref "U1") (pin "6") (pinfunction "OUT1_6") (pintype "passive"))
    )
    (net (code "56") (name "Net-(U1-OUT2)") (class "Default")
      (node (ref "R24") (pin "1") (pinfunction "1_1") (pintype "passive"))
      (node (ref "U1") (pin "7") (pinfunction "OUT2_7") (pintype "passive"))
    )
    (net (code "57") (name "Net-(U1-OUT3)") (class "Default")
      (node (ref "R23") (pin "1") (pinfunction "1_1") (pintype "passive"))
      (node (ref "U1") (pin "8") (pinfunction "OUT3_8") (pintype "passive"))
    )
    (net (code "58") (name "Net-(U1-OUT4)") (class "Default")
      (node (ref "R22") (pin "1") (pinfunction "1_1") (pintype "passive"))
      (node (ref "U1") (pin "9") (pinfunction "OUT4_9") (pintype "passive"))
    )
    (net (code "59") (name "Net-(U1-OUT5)") (class "Default")
      (node (ref "R21") (pin "1") (pinfunction "1_1") (pintype "passive"))
      (node (ref "U1") (pin "10") (pinfunction "OUT5_10") (pintype "passive"))
    )
    (net (code "60") (name "Net-(U1-OUT6)") (class "Default")
      (node (ref "R20") (pin "1") (pinfunction "1_1") (pintype "passive"))
      (node (ref "U1") (pin "11") (pinfunction "OUT6_11") (pintype "passive"))
    )
    (net (code "61") (name "Net-(U1-OUT7)") (class "Default")
      (node (ref "R19") (pin "1") (pinfunction "1_1") (pintype "passive"))
      (node (ref "U1") (pin "12") (pinfunction "OUT7_12") (pintype "passive"))
    )
    (net (code "62") (name "Net-(U1-OUT8)") (class "Default")
      (node (ref "R18") (pin "1") (pinfunction "1_1") (pintype "passive"))
      (node (ref "U1") (pin "13") (pinfunction "OUT8_13") (pintype "passive"))
    )
    (net (code "63") (name "Net-(U1-OUT9)") (class "Default")
      (node (ref "R17") (pin "1") (pinfunction "1_1") (pintype "passive"))
      (node (ref "U1") (pin "14") (pinfunction "OUT9_14") (pintype "passive"))
    )
    (net (code "64") (name "Net-(U1-OUT10)") (class "Default")
      (node (ref "R16") (pin "1") (pinfunction "1_1") (pintype "passive"))
      (node (ref "U1") (pin "15") (pinfunction "OUT10_15") (pintype "passive"))
    )
    (net (code "65") (name "Net-(U1-OUT11)") (class "Default")
      (node (ref "R15") (pin "1") (pinfunction "1_1") (pintype "passive"))
      (node (ref "U1") (pin "16") (pinfunction "OUT11_16") (pintype "passive"))
    )
    (net (code "66") (name "Net-(U1-OUT12)") (class "Default")
      (node (ref "R14") (pin "1") (pinfunction "1_1") (pintype "passive"))
      (node (ref "U1") (pin "17") (pinfunction "OUT12_17") (pintype "passive"))
    )
    (net (code "67") (name "Net-(U1-OUT13)") (class "Default")
      (node (ref "R13") (pin "1") (pinfunction "1_1") (pintype "passive"))
      (node (ref "U1") (pin "18") (pinfunction "OUT13_18") (pintype "passive"))
    )
    (net (code "68") (name "Net-(U1-OUT14)") (class "Default")
      (node (ref "R12") (pin "1") (pinfunction "1_1") (pintype "passive"))
      (node (ref "U1") (pin "19") (pinfunction "OUT14_19") (pintype "passive"))
    )
    (net (code "69") (name "Net-(U1-OUT15)") (class "Default")
      (node (ref "R11") (pin "1") (pinfunction "1_1") (pintype "passive"))
      (node (ref "U1") (pin "20") (pinfunction "OUT15_20") (pintype "passive"))
    )
    (net (code "70") (name "Net-(U1-REXT)") (class "Default")
      (node (ref "R1") (pin "2") (pinfunction "2_2") (pintype "passive"))
      (node (ref "U1") (pin "23") (pinfunction "REXT_23") (pintype "passive"))
    )
    (net (code "71") (name "Net-(U2-OUT0)") (class "Default")
      (node (ref "R42") (pin "1") (pinfunction "1_1") (pintype "passive"))
      (node (ref "U2") (pin "5") (pinfunction "OUT0_5") (pintype "passive"))
    )
    (net (code "72") (name "Net-(U2-OUT1)") (class "Default")
      (node (ref "R41") (pin "1") (pinfunction "1_1") (pintype "passive"))
      (node (ref "U2") (pin "6") (pinfunction "OUT1_6") (pintype "passive"))
    )
    (net (code "73") (name "Net-(U2-OUT2)") (class "Default")
      (node (ref "R40") (pin "1") (pinfunction "1_1") (pintype "passive"))
      (node (ref "U2") (pin "7") (pinfunction "OUT2_7") (pintype "passive"))
    )
    (net (code "74") (name "Net-(U2-OUT3)") (class "Default")
      (node (ref "R39") (pin "1") (pinfunction "1_1") (pintype "passive"))
      (node (ref "U2") (pin "8") (pinfunction "OUT3_8") (pintype "passive"))
    )
    (net (code "75") (name "Net-(U2-OUT4)") (class "Default")
      (node (ref "R38") (pin "1") (pinfunction "1_1") (pintype "passive"))
      (node (ref "U2") (pin "9") (pinfunction "OUT4_9") (pintype "passive"))
    )
    (net (code "76") (name "Net-(U2-OUT5)") (class "Default")
      (node (ref "R37") (pin "1") (pinfunction "1_1") (pintype "passive"))
      (node (ref "U2") (pin "10") (pinfunction "OUT5_10") (pintype "passive"))
    )
    (net (code "77") (name "Net-(U2-OUT6)") (class "Default")
      (node (ref "R36") (pin "1") (pinfunction "1_1") (pintype "passive"))
      (node (ref "U2") (pin "11") (pinfunction "OUT6_11") (pintype "passive"))
    )
    (net (code "78") (name "Net-(U2-OUT7)") (class "Default")
      (node (ref "R35") (pin "1") (pinfunction "1_1") (pintype "passive"))
      (node (ref "U2") (pin "12") (pinfunction "OUT7_12") (pintype "passive"))
    )
    (net (code "79") (name "Net-(U2-OUT8)") (class "Default")
      (node (ref "R34") (pin "1") (pinfunction "1_1") (pintype "passive"))
      (node (ref "U2") (pin "13") (pinfunction "OUT8_13") (pintype "passive"))
    )
    (net (code "80") (name "Net-(U2-OUT9)") (class "Default")
      (node (ref "R33") (pin "1") (pinfunction "1_1") (pintype "passive"))
      (node (ref "U2") (pin "14") (pinfunction "OUT9_14") (pintype "passive"))
    )
    (net (code "81") (name "Net-(U2-OUT10)") (class "Default")
      (node (ref "R32") (pin "1") (pinfunction "1_1") (pintype "passive"))
      (node (ref "U2") (pin "15") (pinfunction "OUT10_15") (pintype "passive"))
    )
    (net (code "82") (name "Net-(U2-OUT11)") (class "Default")
      (node (ref "R31") (pin "1") (pinfunction "1_1") (pintype "passive"))
      (node (ref "U2") (pin "16") (pinfunction "OUT11_16") (pintype "passive"))
    )
    (net (code "83") (name "Net-(U2-OUT12)") (class "Default")
      (node (ref "R30") (pin "1") (pinfunction "1_1") (pintype "passive"))
      (node (ref "U2") (pin "17") (pinfunction "OUT12_17") (pintype "passive"))
    )
    (net (code "84") (name "Net-(U2-OUT13)") (class "Default")
      (node (ref "R29") (pin "1") (pinfunction "1_1") (pintype "passive"))
      (node (ref "U2") (pin "18") (pinfunction "OUT13_18") (pintype "passive"))
    )
    (net (code "85") (name "Net-(U2-OUT14)") (class "Default")
      (node (ref "R28") (pin "1") (pinfunction "1_1") (pintype "passive"))
      (node (ref "U2") (pin "19") (pinfunction "OUT14_19") (pintype "passive"))
    )
    (net (code "86") (name "Net-(U2-OUT15)") (class "Default")
      (node (ref "R27") (pin "1") (pinfunction "1_1") (pintype "passive"))
      (node (ref "U2") (pin "20") (pinfunction "OUT15_20") (pintype "passive"))
    )
    (net (code "87") (name "Net-(U2-REXT)") (class "Default")
      (node (ref "R2") (pin "2") (pinfunction "2_2") (pintype "passive"))
      (node (ref "U2") (pin "23") (pinfunction "REXT_23") (pintype "passive"))
    )
    (net (code "88") (name "VCC_3V3") (class "Default")
      (node (ref "C3") (pin "1") (pinfunction "1_1") (pintype "passive"))
      (node (ref "LED71") (pin "2") (pinfunction "A_2") (pintype "passive"))
      (node (ref "P1") (pin "13") (pinfunction "13_13") (pintype "passive"))
      (node (ref "P1") (pin "14") (pinfunction "14_14") (pintype "passive"))
      (node (ref "Q1") (pin "2") (pinfunction "S_2") (pintype "passive"))
    )
    (net (code "89") (name "unconnected-(U2-SDO-Pad22)") (class "Default")
      (node (ref "U2") (pin "22") (pinfunction "SDO_22") (pintype "passive+no_connect"))
    )
  )
)
